# 473.net
KiCad netlist of a schematic drawn in EAGLE
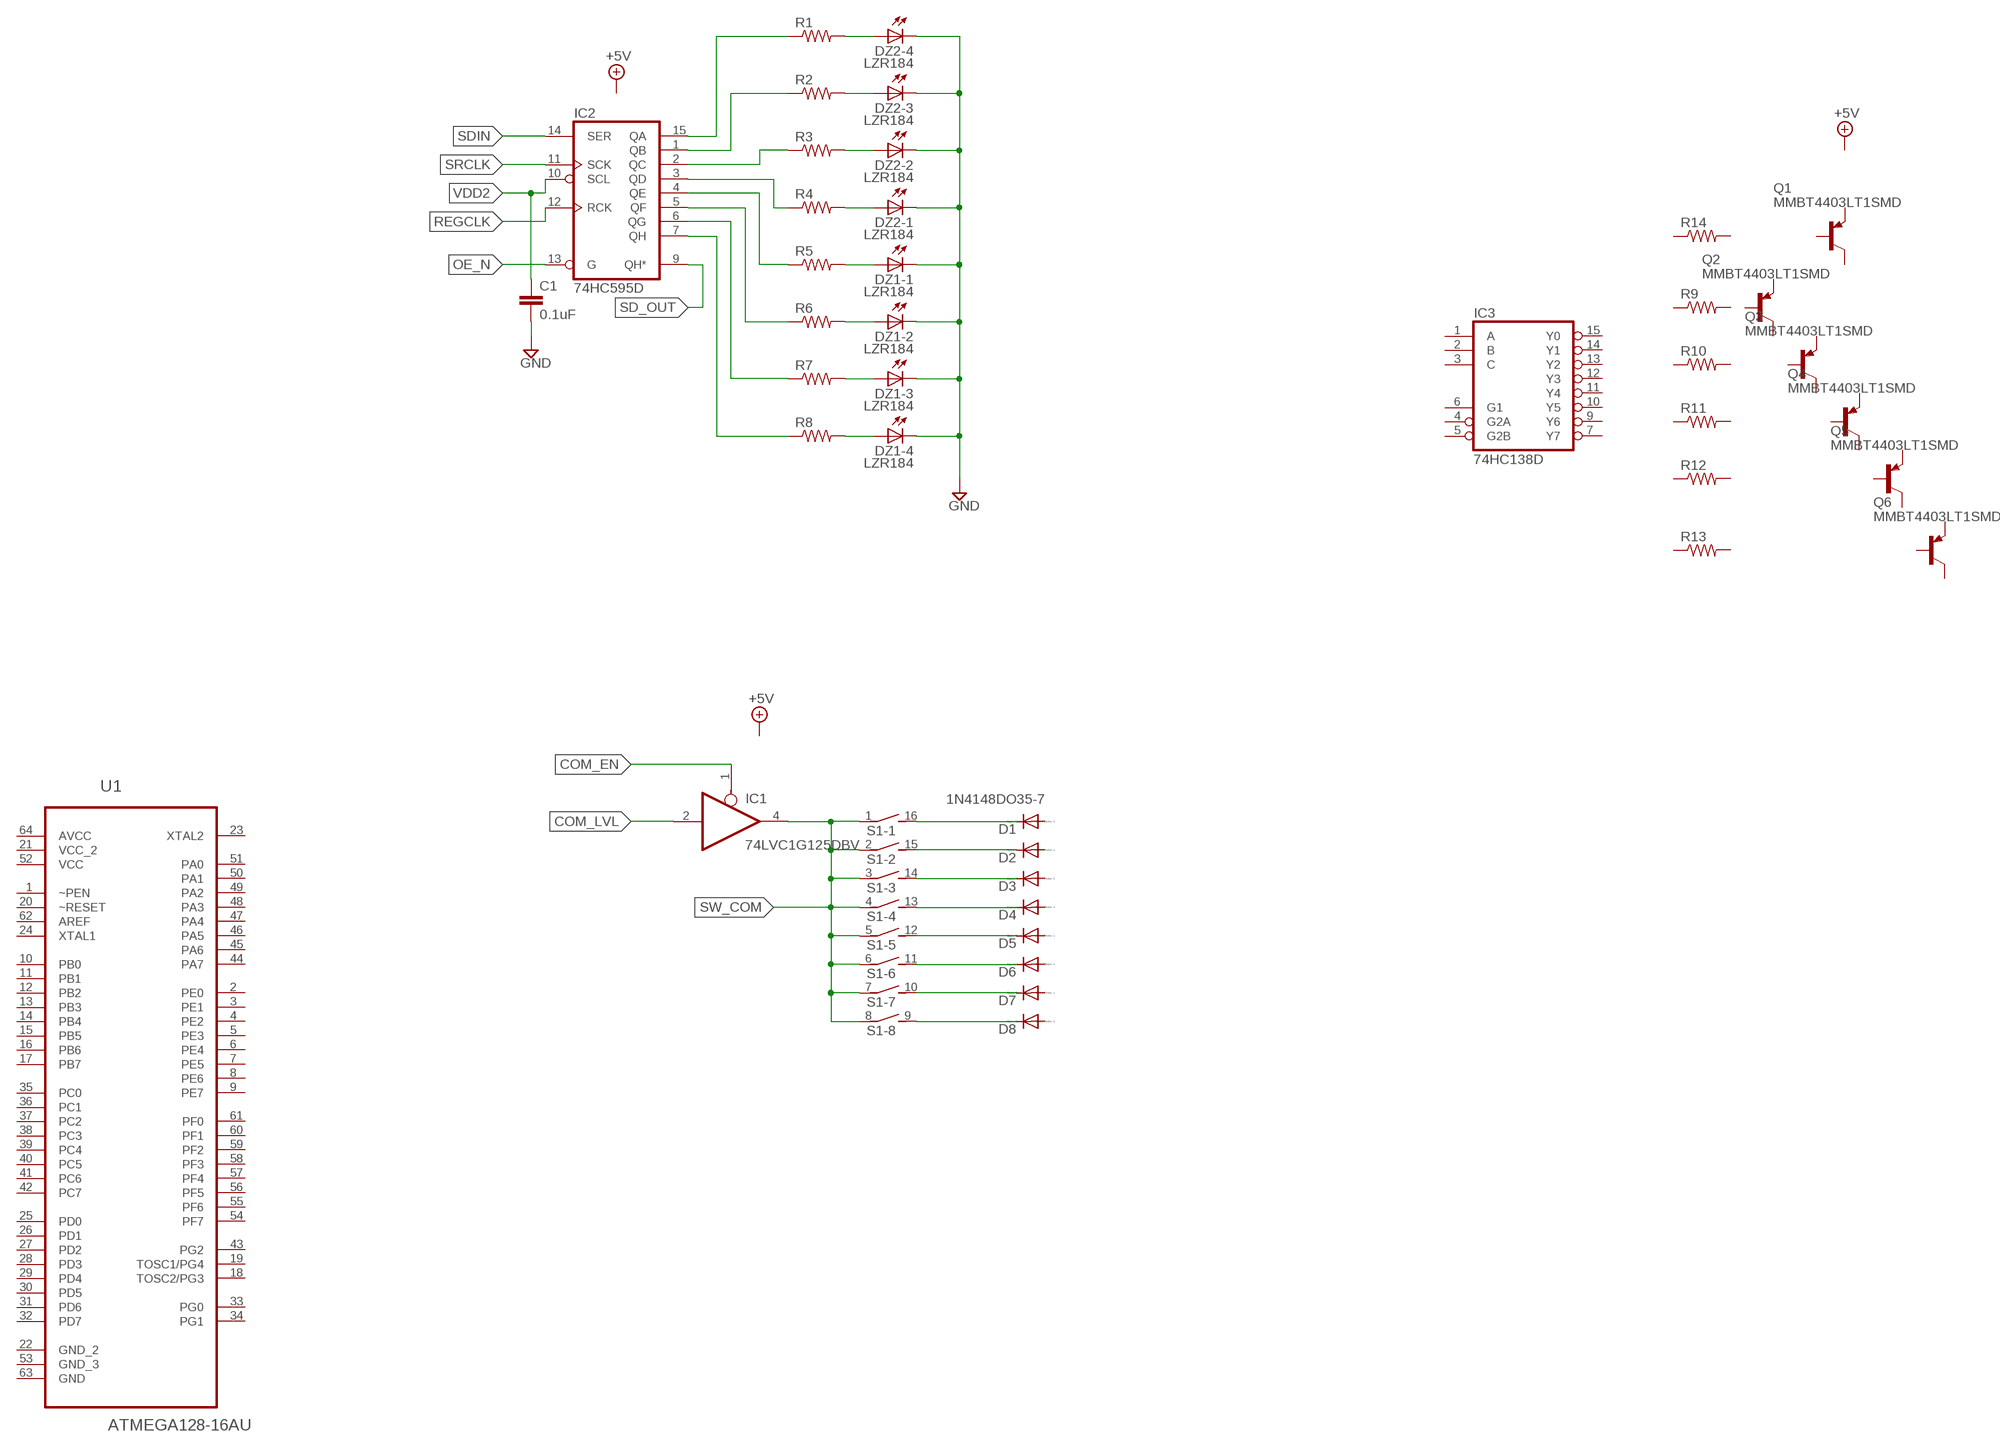
[diagram p0: schematic, sheet 1]

(export (version "E")
  (design (tool "Eeschema 10.0.6"))
  (components
    (comp (ref "C1")
      (value "0.1uF")
      (footprint "eagle-import:C0805")
      (libsource (lib "eagle-import") (part "C-EUC0805"))
    )
    (comp (ref "D1")
      (value "1N4148DO35-7")
      (footprint "eagle-import:DO35-7")
      (libsource (lib "eagle-import") (part "1N4148DO35-7"))
    )
    (comp (ref "D2")
      (value "1N4148DO35-7")
      (footprint "eagle-import:DO35-7")
      (libsource (lib "eagle-import") (part "1N4148DO35-7"))
    )
    (comp (ref "D3")
      (value "1N4148DO35-7")
      (footprint "eagle-import:DO35-7")
      (libsource (lib "eagle-import") (part "1N4148DO35-7"))
    )
    (comp (ref "D4")
      (value "1N4148DO35-7")
      (footprint "eagle-import:DO35-7")
      (libsource (lib "eagle-import") (part "1N4148DO35-7"))
    )
    (comp (ref "D5")
      (value "1N4148DO35-7")
      (footprint "eagle-import:DO35-7")
      (libsource (lib "eagle-import") (part "1N4148DO35-7"))
    )
    (comp (ref "D6")
      (value "1N4148DO35-7")
      (footprint "eagle-import:DO35-7")
      (libsource (lib "eagle-import") (part "1N4148DO35-7"))
    )
    (comp (ref "D7")
      (value "1N4148DO35-7")
      (footprint "eagle-import:DO35-7")
      (libsource (lib "eagle-import") (part "1N4148DO35-7"))
    )
    (comp (ref "D8")
      (value "1N4148DO35-7")
      (footprint "eagle-import:DO35-7")
      (libsource (lib "eagle-import") (part "1N4148DO35-7"))
    )
    (comp (ref "DZ1")
      (value "LZR184")
      (footprint "eagle-import:LZR184")
      (libsource (lib "eagle-import") (part "LZR184"))
    )
    (comp (ref "DZ2")
      (value "LZR184")
      (footprint "eagle-import:LZR184")
      (libsource (lib "eagle-import") (part "LZR184"))
    )
    (comp (ref "IC1")
      (value "74LVC1G125DBV")
      (footprint "eagle-import:SOT23-5")
      (libsource (lib "eagle-import") (part "741G125DBVLVC"))
    )
    (comp (ref "IC2")
      (value "74HC595D")
      (footprint "eagle-import:SO16")
      (libsource (lib "eagle-import") (part "74595DHC"))
    )
    (comp (ref "IC3")
      (value "74HC138D")
      (footprint "eagle-import:SO16")
      (libsource (lib "eagle-import") (part "74138DHC"))
    )
    (comp (ref "Q1")
      (value "MMBT4403LT1SMD")
      (footprint "eagle-import:SOT23-BEC")
      (libsource (lib "eagle-import") (part "MMBT4403SMDLT1"))
    )
    (comp (ref "Q2")
      (value "MMBT4403LT1SMD")
      (footprint "eagle-import:SOT23-BEC")
      (libsource (lib "eagle-import") (part "MMBT4403SMDLT1"))
    )
    (comp (ref "Q3")
      (value "MMBT4403LT1SMD")
      (footprint "eagle-import:SOT23-BEC")
      (libsource (lib "eagle-import") (part "MMBT4403SMDLT1"))
    )
    (comp (ref "Q4")
      (value "MMBT4403LT1SMD")
      (footprint "eagle-import:SOT23-BEC")
      (libsource (lib "eagle-import") (part "MMBT4403SMDLT1"))
    )
    (comp (ref "Q5")
      (value "MMBT4403LT1SMD")
      (footprint "eagle-import:SOT23-BEC")
      (libsource (lib "eagle-import") (part "MMBT4403SMDLT1"))
    )
    (comp (ref "Q6")
      (value "MMBT4403LT1SMD")
      (footprint "eagle-import:SOT23-BEC")
      (libsource (lib "eagle-import") (part "MMBT4403SMDLT1"))
    )
    (comp (ref "R1")
      (value "R-US_R0603")
      (footprint "eagle-import:R0603")
      (libsource (lib "eagle-import") (part "R-US_R0603"))
    )
    (comp (ref "R2")
      (value "R-US_R0603")
      (footprint "eagle-import:R0603")
      (libsource (lib "eagle-import") (part "R-US_R0603"))
    )
    (comp (ref "R3")
      (value "R-US_R0603")
      (footprint "eagle-import:R0603")
      (libsource (lib "eagle-import") (part "R-US_R0603"))
    )
    (comp (ref "R4")
      (value "R-US_R0603")
      (footprint "eagle-import:R0603")
      (libsource (lib "eagle-import") (part "R-US_R0603"))
    )
    (comp (ref "R5")
      (value "R-US_R0603")
      (footprint "eagle-import:R0603")
      (libsource (lib "eagle-import") (part "R-US_R0603"))
    )
    (comp (ref "R6")
      (value "R-US_R0603")
      (footprint "eagle-import:R0603")
      (libsource (lib "eagle-import") (part "R-US_R0603"))
    )
    (comp (ref "R7")
      (value "R-US_R0603")
      (footprint "eagle-import:R0603")
      (libsource (lib "eagle-import") (part "R-US_R0603"))
    )
    (comp (ref "R8")
      (value "R-US_R0603")
      (footprint "eagle-import:R0603")
      (libsource (lib "eagle-import") (part "R-US_R0603"))
    )
    (comp (ref "R9")
      (value "R-US_R0603")
      (footprint "eagle-import:R0603")
      (libsource (lib "eagle-import") (part "R-US_R0603"))
    )
    (comp (ref "R10")
      (value "R-US_R0603")
      (footprint "eagle-import:R0603")
      (libsource (lib "eagle-import") (part "R-US_R0603"))
    )
    (comp (ref "R11")
      (value "R-US_R0603")
      (footprint "eagle-import:R0603")
      (libsource (lib "eagle-import") (part "R-US_R0603"))
    )
    (comp (ref "R12")
      (value "R-US_R0603")
      (footprint "eagle-import:R0603")
      (libsource (lib "eagle-import") (part "R-US_R0603"))
    )
    (comp (ref "R13")
      (value "R-US_R0603")
      (footprint "eagle-import:R0603")
      (libsource (lib "eagle-import") (part "R-US_R0603"))
    )
    (comp (ref "R14")
      (value "R-US_R0603")
      (footprint "eagle-import:R0603")
      (libsource (lib "eagle-import") (part "R-US_R0603"))
    )
    (comp (ref "S1")
      (value "DIP08SB")
      (footprint "eagle-import:DIP08SB")
      (libsource (lib "eagle-import") (part "DIP08SB"))
    )
    (comp (ref "U1")
      (value "ATMEGA128-16AU")
      (footprint "eagle-import:QFP80P1600X1600X120-64N")
      (libsource (lib "eagle-import") (part "ATMEGA128-16AU"))
    )
  )
  (nets
    (net (code "2") (name "/AVCC") (class "Default")
      (node (ref "U1") (pin "64") (pinfunction "AVCC_64") (pintype "power_in"))
    )
    (net (code "3") (name "/VCC") (class "Default")
      (node (ref "U1") (pin "52") (pinfunction "VCC_52") (pintype "power_in"))
    )
    (net (code "4") (name "/VCC_2") (class "Default")
      (node (ref "U1") (pin "21") (pinfunction "VCC_2_21") (pintype "power_in"))
    )
    (net (code "5") (name "COM_EN") (class "Default")
      (node (ref "IC1") (pin "1") (pinfunction "OE_1") (pintype "input"))
    )
    (net (code "6") (name "COM_LVL") (class "Default")
      (node (ref "IC1") (pin "2") (pinfunction "I_2") (pintype "input"))
    )
    (net (code "7") (name "GND") (class "Default")
      (node (ref "C1") (pin "2") (pinfunction "2_2") (pintype "passive"))
      (node (ref "DZ1") (pin "K1") (pinfunction "C_K1") (pintype "passive"))
      (node (ref "DZ1") (pin "K2") (pinfunction "C_K2") (pintype "passive"))
      (node (ref "DZ1") (pin "K3") (pinfunction "C_K3") (pintype "passive"))
      (node (ref "DZ1") (pin "K4") (pinfunction "C_K4") (pintype "passive"))
      (node (ref "DZ2") (pin "K1") (pinfunction "C_K1") (pintype "passive"))
      (node (ref "DZ2") (pin "K2") (pinfunction "C_K2") (pintype "passive"))
      (node (ref "DZ2") (pin "K3") (pinfunction "C_K3") (pintype "passive"))
      (node (ref "DZ2") (pin "K4") (pinfunction "C_K4") (pintype "passive"))
    )
    (net (code "8") (name "Net-(DZ1A-A)") (class "Default")
      (node (ref "DZ1") (pin "A1") (pinfunction "A_A1") (pintype "passive"))
      (node (ref "R5") (pin "2") (pinfunction "2_2") (pintype "passive"))
    )
    (net (code "9") (name "Net-(DZ1B-A)") (class "Default")
      (node (ref "DZ1") (pin "A2") (pinfunction "A_A2") (pintype "passive"))
      (node (ref "R6") (pin "2") (pinfunction "2_2") (pintype "passive"))
    )
    (net (code "10") (name "Net-(DZ1C-A)") (class "Default")
      (node (ref "DZ1") (pin "A3") (pinfunction "A_A3") (pintype "passive"))
      (node (ref "R7") (pin "2") (pinfunction "2_2") (pintype "passive"))
    )
    (net (code "11") (name "Net-(DZ1D-A)") (class "Default")
      (node (ref "DZ1") (pin "A4") (pinfunction "A_A4") (pintype "passive"))
      (node (ref "R8") (pin "2") (pinfunction "2_2") (pintype "passive"))
    )
    (net (code "12") (name "Net-(DZ2A-A)") (class "Default")
      (node (ref "DZ2") (pin "A1") (pinfunction "A_A1") (pintype "passive"))
      (node (ref "R4") (pin "2") (pinfunction "2_2") (pintype "passive"))
    )
    (net (code "13") (name "Net-(DZ2B-A)") (class "Default")
      (node (ref "DZ2") (pin "A2") (pinfunction "A_A2") (pintype "passive"))
      (node (ref "R3") (pin "2") (pinfunction "2_2") (pintype "passive"))
    )
    (net (code "14") (name "Net-(DZ2C-A)") (class "Default")
      (node (ref "DZ2") (pin "A3") (pinfunction "A_A3") (pintype "passive"))
      (node (ref "R2") (pin "2") (pinfunction "2_2") (pintype "passive"))
    )
    (net (code "15") (name "Net-(DZ2D-A)") (class "Default")
      (node (ref "DZ2") (pin "A4") (pinfunction "A_A4") (pintype "passive"))
      (node (ref "R1") (pin "2") (pinfunction "2_2") (pintype "passive"))
    )
    (net (code "16") (name "Net-(IC2A-QA)") (class "Default")
      (node (ref "IC2") (pin "15") (pinfunction "QA_15") (pintype "tri_state"))
      (node (ref "R1") (pin "1") (pinfunction "1_1") (pintype "passive"))
    )
    (net (code "17") (name "Net-(IC2A-QB)") (class "Default")
      (node (ref "IC2") (pin "1") (pinfunction "QB_1") (pintype "tri_state"))
      (node (ref "R2") (pin "1") (pinfunction "1_1") (pintype "passive"))
    )
    (net (code "18") (name "Net-(IC2A-QC)") (class "Default")
      (node (ref "IC2") (pin "2") (pinfunction "QC_2") (pintype "tri_state"))
      (node (ref "R3") (pin "1") (pinfunction "1_1") (pintype "passive"))
    )
    (net (code "19") (name "Net-(IC2A-QD)") (class "Default")
      (node (ref "IC2") (pin "3") (pinfunction "QD_3") (pintype "tri_state"))
      (node (ref "R4") (pin "1") (pinfunction "1_1") (pintype "passive"))
    )
    (net (code "20") (name "Net-(IC2A-QE)") (class "Default")
      (node (ref "IC2") (pin "4") (pinfunction "QE_4") (pintype "tri_state"))
      (node (ref "R5") (pin "1") (pinfunction "1_1") (pintype "passive"))
    )
    (net (code "21") (name "Net-(IC2A-QF)") (class "Default")
      (node (ref "IC2") (pin "5") (pinfunction "QF_5") (pintype "tri_state"))
      (node (ref "R6") (pin "1") (pinfunction "1_1") (pintype "passive"))
    )
    (net (code "22") (name "Net-(IC2A-QG)") (class "Default")
      (node (ref "IC2") (pin "6") (pinfunction "QG_6") (pintype "tri_state"))
      (node (ref "R7") (pin "1") (pinfunction "1_1") (pintype "passive"))
    )
    (net (code "23") (name "Net-(IC2A-QH)") (class "Default")
      (node (ref "IC2") (pin "7") (pinfunction "QH_7") (pintype "tri_state"))
      (node (ref "R8") (pin "1") (pinfunction "1_1") (pintype "passive"))
    )
    (net (code "24") (name "Net-(S1A-2)") (class "Default")
      (node (ref "D1") (pin "C") (pinfunction "C_C") (pintype "passive"))
      (node (ref "S1") (pin "16") (pinfunction "2_16") (pintype "passive"))
    )
    (net (code "25") (name "Net-(S1B-2)") (class "Default")
      (node (ref "D2") (pin "C") (pinfunction "C_C") (pintype "passive"))
      (node (ref "S1") (pin "15") (pinfunction "2_15") (pintype "passive"))
    )
    (net (code "26") (name "Net-(S1C-2)") (class "Default")
      (node (ref "D3") (pin "C") (pinfunction "C_C") (pintype "passive"))
      (node (ref "S1") (pin "14") (pinfunction "2_14") (pintype "passive"))
    )
    (net (code "27") (name "Net-(S1D-2)") (class "Default")
      (node (ref "D4") (pin "C") (pinfunction "C_C") (pintype "passive"))
      (node (ref "S1") (pin "13") (pinfunction "2_13") (pintype "passive"))
    )
    (net (code "28") (name "Net-(S1E-2)") (class "Default")
      (node (ref "D5") (pin "C") (pinfunction "C_C") (pintype "passive"))
      (node (ref "S1") (pin "12") (pinfunction "2_12") (pintype "passive"))
    )
    (net (code "29") (name "Net-(S1F-2)") (class "Default")
      (node (ref "D6") (pin "C") (pinfunction "C_C") (pintype "passive"))
      (node (ref "S1") (pin "11") (pinfunction "2_11") (pintype "passive"))
    )
    (net (code "30") (name "Net-(S1G-2)") (class "Default")
      (node (ref "D7") (pin "C") (pinfunction "C_C") (pintype "passive"))
      (node (ref "S1") (pin "10") (pinfunction "2_10") (pintype "passive"))
    )
    (net (code "31") (name "Net-(S1H-2)") (class "Default")
      (node (ref "D8") (pin "C") (pinfunction "C_C") (pintype "passive"))
      (node (ref "S1") (pin "9") (pinfunction "2_9") (pintype "passive"))
    )
    (net (code "32") (name "OE_N") (class "Default")
      (node (ref "IC2") (pin "13") (pinfunction "G_13") (pintype "input"))
    )
    (net (code "33") (name "REGCLK") (class "Default")
      (node (ref "IC2") (pin "12") (pinfunction "RCK_12") (pintype "input"))
    )
    (net (code "34") (name "SDIN") (class "Default")
      (node (ref "IC2") (pin "14") (pinfunction "SER_14") (pintype "input"))
    )
    (net (code "35") (name "SD_OUT") (class "Default")
      (node (ref "IC2") (pin "9") (pinfunction "QH*_9") (pintype "tri_state"))
    )
    (net (code "36") (name "SRCLK") (class "Default")
      (node (ref "IC2") (pin "11") (pinfunction "SCK_11") (pintype "input"))
    )
    (net (code "37") (name "SW_COM") (class "Default")
      (node (ref "IC1") (pin "4") (pinfunction "O_4") (pintype "tri_state"))
      (node (ref "S1") (pin "1") (pinfunction "1_1") (pintype "passive"))
      (node (ref "S1") (pin "2") (pinfunction "1_2") (pintype "passive"))
      (node (ref "S1") (pin "3") (pinfunction "1_3") (pintype "passive"))
      (node (ref "S1") (pin "4") (pinfunction "1_4") (pintype "passive"))
      (node (ref "S1") (pin "5") (pinfunction "1_5") (pintype "passive"))
      (node (ref "S1") (pin "6") (pinfunction "1_6") (pintype "passive"))
      (node (ref "S1") (pin "7") (pinfunction "1_7") (pintype "passive"))
      (node (ref "S1") (pin "8") (pinfunction "1_8") (pintype "passive"))
    )
    (net (code "38") (name "VDD2") (class "Default")
      (node (ref "C1") (pin "1") (pinfunction "1_1") (pintype "passive"))
      (node (ref "IC2") (pin "10") (pinfunction "SCL_10") (pintype "input"))
    )
    (net (code "39") (name "unconnected-(D1-PadA)") (class "Default")
      (node (ref "D1") (pin "A") (pinfunction "A_A") (pintype "passive"))
    )
    (net (code "40") (name "unconnected-(D2-PadA)") (class "Default")
      (node (ref "D2") (pin "A") (pinfunction "A_A") (pintype "passive"))
    )
    (net (code "41") (name "unconnected-(D3-PadA)") (class "Default")
      (node (ref "D3") (pin "A") (pinfunction "A_A") (pintype "passive"))
    )
    (net (code "42") (name "unconnected-(D4-PadA)") (class "Default")
      (node (ref "D4") (pin "A") (pinfunction "A_A") (pintype "passive"))
    )
    (net (code "43") (name "unconnected-(D5-PadA)") (class "Default")
      (node (ref "D5") (pin "A") (pinfunction "A_A") (pintype "passive"))
    )
    (net (code "44") (name "unconnected-(D6-PadA)") (class "Default")
      (node (ref "D6") (pin "A") (pinfunction "A_A") (pintype "passive"))
    )
    (net (code "45") (name "unconnected-(D7-PadA)") (class "Default")
      (node (ref "D7") (pin "A") (pinfunction "A_A") (pintype "passive"))
    )
    (net (code "46") (name "unconnected-(D8-PadA)") (class "Default")
      (node (ref "D8") (pin "A") (pinfunction "A_A") (pintype "passive"))
    )
    (net (code "47") (name "unconnected-(IC3A-A-Pad1)") (class "Default")
      (node (ref "IC3") (pin "1") (pinfunction "A_1") (pintype "input"))
    )
    (net (code "48") (name "unconnected-(IC3A-B-Pad2)") (class "Default")
      (node (ref "IC3") (pin "2") (pinfunction "B_2") (pintype "input"))
    )
    (net (code "49") (name "unconnected-(IC3A-C-Pad3)") (class "Default")
      (node (ref "IC3") (pin "3") (pinfunction "C_3") (pintype "input"))
    )
    (net (code "50") (name "unconnected-(IC3A-G1-Pad6)") (class "Default")
      (node (ref "IC3") (pin "6") (pinfunction "G1_6") (pintype "input"))
    )
    (net (code "51") (name "unconnected-(IC3A-G2A-Pad4)") (class "Default")
      (node (ref "IC3") (pin "4") (pinfunction "G2A_4") (pintype "input"))
    )
    (net (code "52") (name "unconnected-(IC3A-G2B-Pad5)") (class "Default")
      (node (ref "IC3") (pin "5") (pinfunction "G2B_5") (pintype "input"))
    )
    (net (code "53") (name "unconnected-(IC3A-Y0-Pad15)") (class "Default")
      (node (ref "IC3") (pin "15") (pinfunction "Y0_15") (pintype "output"))
    )
    (net (code "54") (name "unconnected-(IC3A-Y1-Pad14)") (class "Default")
      (node (ref "IC3") (pin "14") (pinfunction "Y1_14") (pintype "output"))
    )
    (net (code "55") (name "unconnected-(IC3A-Y2-Pad13)") (class "Default")
      (node (ref "IC3") (pin "13") (pinfunction "Y2_13") (pintype "output"))
    )
    (net (code "56") (name "unconnected-(IC3A-Y3-Pad12)") (class "Default")
      (node (ref "IC3") (pin "12") (pinfunction "Y3_12") (pintype "output"))
    )
    (net (code "57") (name "unconnected-(IC3A-Y4-Pad11)") (class "Default")
      (node (ref "IC3") (pin "11") (pinfunction "Y4_11") (pintype "output"))
    )
    (net (code "58") (name "unconnected-(IC3A-Y5-Pad10)") (class "Default")
      (node (ref "IC3") (pin "10") (pinfunction "Y5_10") (pintype "output"))
    )
    (net (code "59") (name "unconnected-(IC3A-Y6-Pad9)") (class "Default")
      (node (ref "IC3") (pin "9") (pinfunction "Y6_9") (pintype "output"))
    )
    (net (code "60") (name "unconnected-(IC3A-Y7-Pad7)") (class "Default")
      (node (ref "IC3") (pin "7") (pinfunction "Y7_7") (pintype "output"))
    )
    (net (code "61") (name "unconnected-(Q1-PadB)") (class "Default")
      (node (ref "Q1") (pin "B") (pinfunction "B_B") (pintype "passive"))
    )
    (net (code "62") (name "unconnected-(Q1-PadC)") (class "Default")
      (node (ref "Q1") (pin "C") (pinfunction "C_C") (pintype "passive"))
    )
    (net (code "63") (name "unconnected-(Q1-PadE)") (class "Default")
      (node (ref "Q1") (pin "E") (pinfunction "E_E") (pintype "passive"))
    )
    (net (code "64") (name "unconnected-(Q2-PadB)") (class "Default")
      (node (ref "Q2") (pin "B") (pinfunction "B_B") (pintype "passive"))
    )
    (net (code "65") (name "unconnected-(Q2-PadC)") (class "Default")
      (node (ref "Q2") (pin "C") (pinfunction "C_C") (pintype "passive"))
    )
    (net (code "66") (name "unconnected-(Q2-PadE)") (class "Default")
      (node (ref "Q2") (pin "E") (pinfunction "E_E") (pintype "passive"))
    )
    (net (code "67") (name "unconnected-(Q3-PadB)") (class "Default")
      (node (ref "Q3") (pin "B") (pinfunction "B_B") (pintype "passive"))
    )
    (net (code "68") (name "unconnected-(Q3-PadC)") (class "Default")
      (node (ref "Q3") (pin "C") (pinfunction "C_C") (pintype "passive"))
    )
    (net (code "69") (name "unconnected-(Q3-PadE)") (class "Default")
      (node (ref "Q3") (pin "E") (pinfunction "E_E") (pintype "passive"))
    )
    (net (code "70") (name "unconnected-(Q4-PadB)") (class "Default")
      (node (ref "Q4") (pin "B") (pinfunction "B_B") (pintype "passive"))
    )
    (net (code "71") (name "unconnected-(Q4-PadC)") (class "Default")
      (node (ref "Q4") (pin "C") (pinfunction "C_C") (pintype "passive"))
    )
    (net (code "72") (name "unconnected-(Q4-PadE)") (class "Default")
      (node (ref "Q4") (pin "E") (pinfunction "E_E") (pintype "passive"))
    )
    (net (code "73") (name "unconnected-(Q5-PadB)") (class "Default")
      (node (ref "Q5") (pin "B") (pinfunction "B_B") (pintype "passive"))
    )
    (net (code "74") (name "unconnected-(Q5-PadC)") (class "Default")
      (node (ref "Q5") (pin "C") (pinfunction "C_C") (pintype "passive"))
    )
    (net (code "75") (name "unconnected-(Q5-PadE)") (class "Default")
      (node (ref "Q5") (pin "E") (pinfunction "E_E") (pintype "passive"))
    )
    (net (code "76") (name "unconnected-(Q6-PadB)") (class "Default")
      (node (ref "Q6") (pin "B") (pinfunction "B_B") (pintype "passive"))
    )
    (net (code "77") (name "unconnected-(Q6-PadC)") (class "Default")
      (node (ref "Q6") (pin "C") (pinfunction "C_C") (pintype "passive"))
    )
    (net (code "78") (name "unconnected-(Q6-PadE)") (class "Default")
      (node (ref "Q6") (pin "E") (pinfunction "E_E") (pintype "passive"))
    )
    (net (code "79") (name "unconnected-(R9-Pad1)") (class "Default")
      (node (ref "R9") (pin "1") (pinfunction "1_1") (pintype "passive"))
    )
    (net (code "80") (name "unconnected-(R9-Pad2)") (class "Default")
      (node (ref "R9") (pin "2") (pinfunction "2_2") (pintype "passive"))
    )
    (net (code "81") (name "unconnected-(R10-Pad1)") (class "Default")
      (node (ref "R10") (pin "1") (pinfunction "1_1") (pintype "passive"))
    )
    (net (code "82") (name "unconnected-(R10-Pad2)") (class "Default")
      (node (ref "R10") (pin "2") (pinfunction "2_2") (pintype "passive"))
    )
    (net (code "83") (name "unconnected-(R11-Pad1)") (class "Default")
      (node (ref "R11") (pin "1") (pinfunction "1_1") (pintype "passive"))
    )
    (net (code "84") (name "unconnected-(R11-Pad2)") (class "Default")
      (node (ref "R11") (pin "2") (pinfunction "2_2") (pintype "passive"))
    )
    (net (code "85") (name "unconnected-(R12-Pad1)") (class "Default")
      (node (ref "R12") (pin "1") (pinfunction "1_1") (pintype "passive"))
    )
    (net (code "86") (name "unconnected-(R12-Pad2)") (class "Default")
      (node (ref "R12") (pin "2") (pinfunction "2_2") (pintype "passive"))
    )
    (net (code "87") (name "unconnected-(R13-Pad1)") (class "Default")
      (node (ref "R13") (pin "1") (pinfunction "1_1") (pintype "passive"))
    )
    (net (code "88") (name "unconnected-(R13-Pad2)") (class "Default")
      (node (ref "R13") (pin "2") (pinfunction "2_2") (pintype "passive"))
    )
    (net (code "89") (name "unconnected-(R14-Pad1)") (class "Default")
      (node (ref "R14") (pin "1") (pinfunction "1_1") (pintype "passive"))
    )
    (net (code "90") (name "unconnected-(R14-Pad2)") (class "Default")
      (node (ref "R14") (pin "2") (pinfunction "2_2") (pintype "passive"))
    )
    (net (code "91") (name "unconnected-(U1-AREF-Pad62)") (class "Default")
      (node (ref "U1") (pin "62") (pinfunction "AREF_62") (pintype "input"))
    )
    (net (code "92") (name "unconnected-(U1-GND-Pad63)") (class "Default")
      (node (ref "U1") (pin "63") (pinfunction "GND_63") (pintype "passive"))
    )
    (net (code "93") (name "unconnected-(U1-GND_2-Pad22)") (class "Default")
      (node (ref "U1") (pin "22") (pinfunction "GND_2_22") (pintype "passive"))
    )
    (net (code "94") (name "unconnected-(U1-GND_3-Pad53)") (class "Default")
      (node (ref "U1") (pin "53") (pinfunction "GND_3_53") (pintype "passive"))
    )
    (net (code "95") (name "unconnected-(U1-PA0-Pad51)") (class "Default")
      (node (ref "U1") (pin "51") (pinfunction "PA0_51") (pintype "bidirectional"))
    )
    (net (code "96") (name "unconnected-(U1-PA1-Pad50)") (class "Default")
      (node (ref "U1") (pin "50") (pinfunction "PA1_50") (pintype "bidirectional"))
    )
    (net (code "97") (name "unconnected-(U1-PA2-Pad49)") (class "Default")
      (node (ref "U1") (pin "49") (pinfunction "PA2_49") (pintype "bidirectional"))
    )
    (net (code "98") (name "unconnected-(U1-PA3-Pad48)") (class "Default")
      (node (ref "U1") (pin "48") (pinfunction "PA3_48") (pintype "bidirectional"))
    )
    (net (code "99") (name "unconnected-(U1-PA4-Pad47)") (class "Default")
      (node (ref "U1") (pin "47") (pinfunction "PA4_47") (pintype "bidirectional"))
    )
    (net (code "100") (name "unconnected-(U1-PA5-Pad46)") (class "Default")
      (node (ref "U1") (pin "46") (pinfunction "PA5_46") (pintype "bidirectional"))
    )
    (net (code "101") (name "unconnected-(U1-PA6-Pad45)") (class "Default")
      (node (ref "U1") (pin "45") (pinfunction "PA6_45") (pintype "bidirectional"))
    )
    (net (code "102") (name "unconnected-(U1-PA7-Pad44)") (class "Default")
      (node (ref "U1") (pin "44") (pinfunction "PA7_44") (pintype "bidirectional"))
    )
    (net (code "103") (name "unconnected-(U1-PB0-Pad10)") (class "Default")
      (node (ref "U1") (pin "10") (pinfunction "PB0_10") (pintype "bidirectional"))
    )
    (net (code "104") (name "unconnected-(U1-PB1-Pad11)") (class "Default")
      (node (ref "U1") (pin "11") (pinfunction "PB1_11") (pintype "bidirectional"))
    )
    (net (code "105") (name "unconnected-(U1-PB2-Pad12)") (class "Default")
      (node (ref "U1") (pin "12") (pinfunction "PB2_12") (pintype "bidirectional"))
    )
    (net (code "106") (name "unconnected-(U1-PB3-Pad13)") (class "Default")
      (node (ref "U1") (pin "13") (pinfunction "PB3_13") (pintype "bidirectional"))
    )
    (net (code "107") (name "unconnected-(U1-PB4-Pad14)") (class "Default")
      (node (ref "U1") (pin "14") (pinfunction "PB4_14") (pintype "bidirectional"))
    )
    (net (code "108") (name "unconnected-(U1-PB5-Pad15)") (class "Default")
      (node (ref "U1") (pin "15") (pinfunction "PB5_15") (pintype "bidirectional"))
    )
    (net (code "109") (name "unconnected-(U1-PB6-Pad16)") (class "Default")
      (node (ref "U1") (pin "16") (pinfunction "PB6_16") (pintype "bidirectional"))
    )
    (net (code "110") (name "unconnected-(U1-PB7-Pad17)") (class "Default")
      (node (ref "U1") (pin "17") (pinfunction "PB7_17") (pintype "bidirectional"))
    )
    (net (code "111") (name "unconnected-(U1-PC0-Pad35)") (class "Default")
      (node (ref "U1") (pin "35") (pinfunction "PC0_35") (pintype "bidirectional"))
    )
    (net (code "112") (name "unconnected-(U1-PC1-Pad36)") (class "Default")
      (node (ref "U1") (pin "36") (pinfunction "PC1_36") (pintype "bidirectional"))
    )
    (net (code "113") (name "unconnected-(U1-PC2-Pad37)") (class "Default")
      (node (ref "U1") (pin "37") (pinfunction "PC2_37") (pintype "bidirectional"))
    )
    (net (code "114") (name "unconnected-(U1-PC3-Pad38)") (class "Default")
      (node (ref "U1") (pin "38") (pinfunction "PC3_38") (pintype "bidirectional"))
    )
    (net (code "115") (name "unconnected-(U1-PC4-Pad39)") (class "Default")
      (node (ref "U1") (pin "39") (pinfunction "PC4_39") (pintype "bidirectional"))
    )
    (net (code "116") (name "unconnected-(U1-PC5-Pad40)") (class "Default")
      (node (ref "U1") (pin "40") (pinfunction "PC5_40") (pintype "bidirectional"))
    )
    (net (code "117") (name "unconnected-(U1-PC6-Pad41)") (class "Default")
      (node (ref "U1") (pin "41") (pinfunction "PC6_41") (pintype "bidirectional"))
    )
    (net (code "118") (name "unconnected-(U1-PC7-Pad42)") (class "Default")
      (node (ref "U1") (pin "42") (pinfunction "PC7_42") (pintype "bidirectional"))
    )
    (net (code "119") (name "unconnected-(U1-PD0-Pad25)") (class "Default")
      (node (ref "U1") (pin "25") (pinfunction "PD0_25") (pintype "bidirectional"))
    )
    (net (code "120") (name "unconnected-(U1-PD1-Pad26)") (class "Default")
      (node (ref "U1") (pin "26") (pinfunction "PD1_26") (pintype "bidirectional"))
    )
    (net (code "121") (name "unconnected-(U1-PD2-Pad27)") (class "Default")
      (node (ref "U1") (pin "27") (pinfunction "PD2_27") (pintype "bidirectional"))
    )
    (net (code "122") (name "unconnected-(U1-PD3-Pad28)") (class "Default")
      (node (ref "U1") (pin "28") (pinfunction "PD3_28") (pintype "bidirectional"))
    )
    (net (code "123") (name "unconnected-(U1-PD4-Pad29)") (class "Default")
      (node (ref "U1") (pin "29") (pinfunction "PD4_29") (pintype "bidirectional"))
    )
    (net (code "124") (name "unconnected-(U1-PD5-Pad30)") (class "Default")
      (node (ref "U1") (pin "30") (pinfunction "PD5_30") (pintype "bidirectional"))
    )
    (net (code "125") (name "unconnected-(U1-PD6-Pad31)") (class "Default")
      (node (ref "U1") (pin "31") (pinfunction "PD6_31") (pintype "bidirectional"))
    )
    (net (code "126") (name "unconnected-(U1-PD7-Pad32)") (class "Default")
      (node (ref "U1") (pin "32") (pinfunction "PD7_32") (pintype "bidirectional"))
    )
    (net (code "127") (name "unconnected-(U1-PE0-Pad2)") (class "Default")
      (node (ref "U1") (pin "2") (pinfunction "PE0_2") (pintype "bidirectional"))
    )
    (net (code "128") (name "unconnected-(U1-PE1-Pad3)") (class "Default")
      (node (ref "U1") (pin "3") (pinfunction "PE1_3") (pintype "bidirectional"))
    )
    (net (code "129") (name "unconnected-(U1-PE2-Pad4)") (class "Default")
      (node (ref "U1") (pin "4") (pinfunction "PE2_4") (pintype "bidirectional"))
    )
    (net (code "130") (name "unconnected-(U1-PE3-Pad5)") (class "Default")
      (node (ref "U1") (pin "5") (pinfunction "PE3_5") (pintype "bidirectional"))
    )
    (net (code "131") (name "unconnected-(U1-PE4-Pad6)") (class "Default")
      (node (ref "U1") (pin "6") (pinfunction "PE4_6") (pintype "bidirectional"))
    )
    (net (code "132") (name "unconnected-(U1-PE5-Pad7)") (class "Default")
      (node (ref "U1") (pin "7") (pinfunction "PE5_7") (pintype "bidirectional"))
    )
    (net (code "133") (name "unconnected-(U1-PE6-Pad8)") (class "Default")
      (node (ref "U1") (pin "8") (pinfunction "PE6_8") (pintype "bidirectional"))
    )
    (net (code "134") (name "unconnected-(U1-PE7-Pad9)") (class "Default")
      (node (ref "U1") (pin "9") (pinfunction "PE7_9") (pintype "bidirectional"))
    )
    (net (code "135") (name "unconnected-(U1-PF0-Pad61)") (class "Default")
      (node (ref "U1") (pin "61") (pinfunction "PF0_61") (pintype "bidirectional"))
    )
    (net (code "136") (name "unconnected-(U1-PF1-Pad60)") (class "Default")
      (node (ref "U1") (pin "60") (pinfunction "PF1_60") (pintype "bidirectional"))
    )
    (net (code "137") (name "unconnected-(U1-PF2-Pad59)") (class "Default")
      (node (ref "U1") (pin "59") (pinfunction "PF2_59") (pintype "bidirectional"))
    )
    (net (code "138") (name "unconnected-(U1-PF3-Pad58)") (class "Default")
      (node (ref "U1") (pin "58") (pinfunction "PF3_58") (pintype "bidirectional"))
    )
    (net (code "139") (name "unconnected-(U1-PF4-Pad57)") (class "Default")
      (node (ref "U1") (pin "57") (pinfunction "PF4_57") (pintype "bidirectional"))
    )
    (net (code "140") (name "unconnected-(U1-PF5-Pad56)") (class "Default")
      (node (ref "U1") (pin "56") (pinfunction "PF5_56") (pintype "bidirectional"))
    )
    (net (code "141") (name "unconnected-(U1-PF6-Pad55)") (class "Default")
      (node (ref "U1") (pin "55") (pinfunction "PF6_55") (pintype "bidirectional"))
    )
    (net (code "142") (name "unconnected-(U1-PF7-Pad54)") (class "Default")
      (node (ref "U1") (pin "54") (pinfunction "PF7_54") (pintype "bidirectional"))
    )
    (net (code "143") (name "unconnected-(U1-PG0-Pad33)") (class "Default")
      (node (ref "U1") (pin "33") (pinfunction "PG0_33") (pintype "bidirectional"))
    )
    (net (code "144") (name "unconnected-(U1-PG1-Pad34)") (class "Default")
      (node (ref "U1") (pin "34") (pinfunction "PG1_34") (pintype "bidirectional"))
    )
    (net (code "145") (name "unconnected-(U1-PG2-Pad43)") (class "Default")
      (node (ref "U1") (pin "43") (pinfunction "PG2_43") (pintype "bidirectional"))
    )
    (net (code "146") (name "unconnected-(U1-TOSC1{slash}PG4-Pad19)") (class "Default")
      (node (ref "U1") (pin "19") (pinfunction "TOSC1/PG4_19") (pintype "bidirectional"))
    )
    (net (code "147") (name "unconnected-(U1-TOSC2{slash}PG3-Pad18)") (class "Default")
      (node (ref "U1") (pin "18") (pinfunction "TOSC2/PG3_18") (pintype "bidirectional"))
    )
    (net (code "148") (name "unconnected-(U1-XTAL1-Pad24)") (class "Default")
      (node (ref "U1") (pin "24") (pinfunction "XTAL1_24") (pintype "input"))
    )
    (net (code "149") (name "unconnected-(U1-XTAL2-Pad23)") (class "Default")
      (node (ref "U1") (pin "23") (pinfunction "XTAL2_23") (pintype "output"))
    )
    (net (code "150") (name "unconnected-(U1-~{PEN}-Pad1)") (class "Default")
      (node (ref "U1") (pin "1") (pinfunction "~{PEN}_1") (pintype "input"))
    )
    (net (code "151") (name "unconnected-(U1-~{RESET}-Pad20)") (class "Default")
      (node (ref "U1") (pin "20") (pinfunction "~{RESET}_20") (pintype "input"))
    )
  )
)
